# MainSheet.net
KiCad netlist of a schematic drawn in Altium Designer
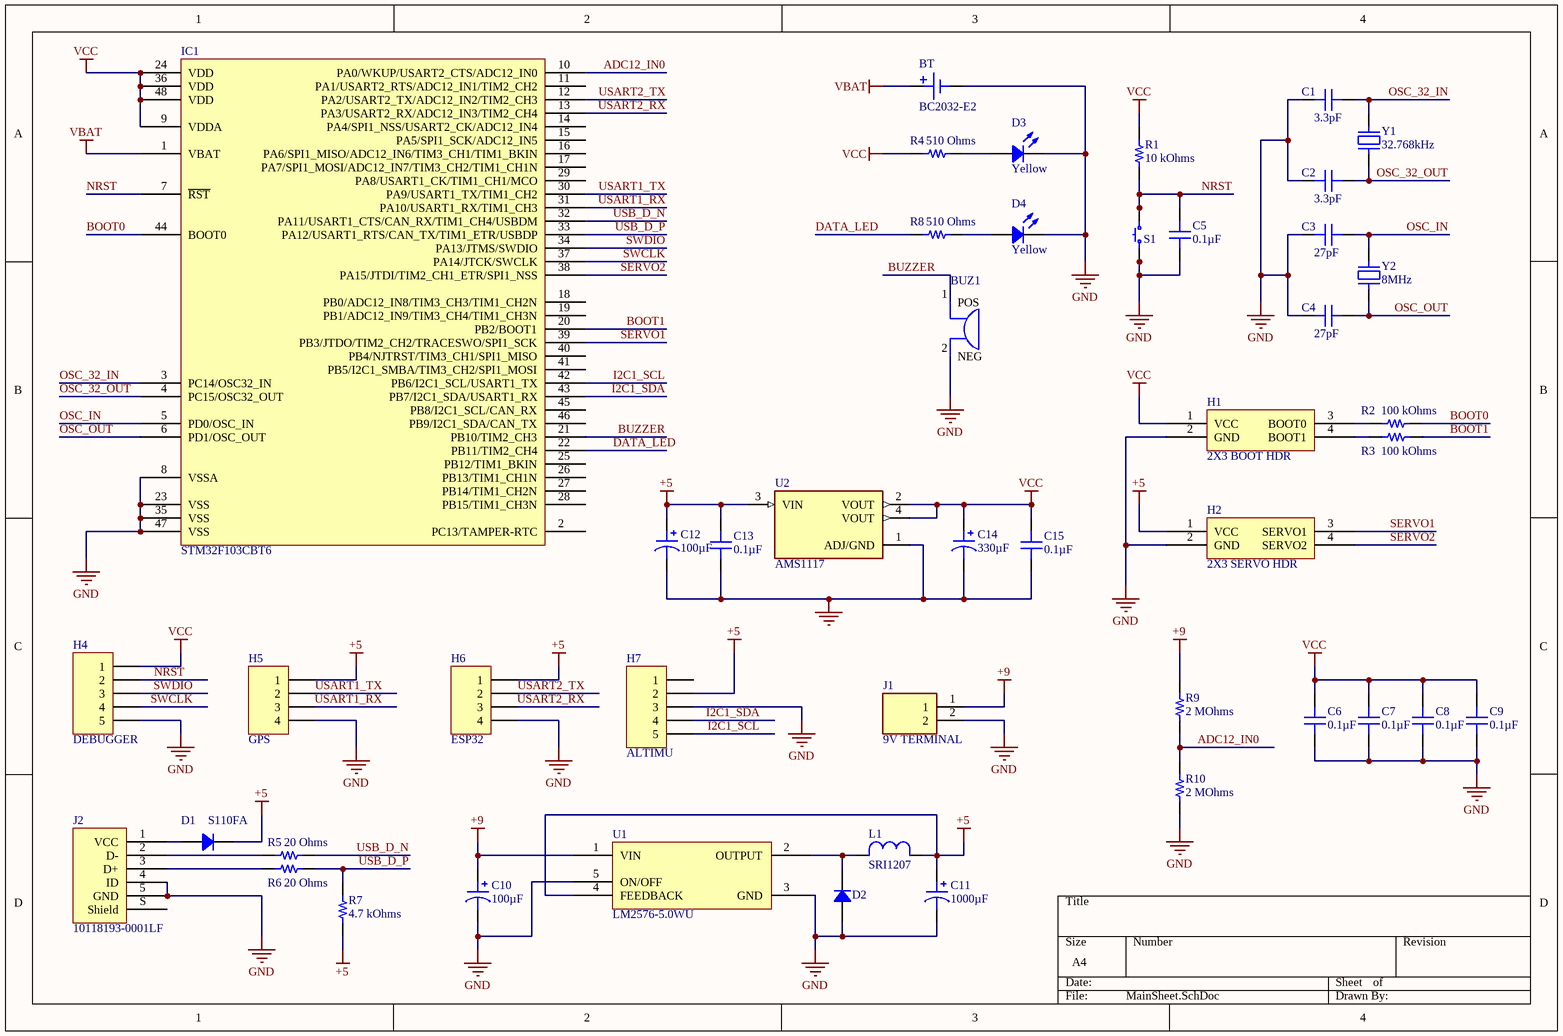
[diagram p0: MainSheet.SchDoc]

(export (version "E")
  (design (tool "Eeschema 10.0.6"))
  (components
    (comp (ref "BT")
      (value "BC2032-E2")
      (footprint "MPD_BC2032-E2")
      (description "BATTERY HOLDER COIN 20MM PC PIN")
      (fields (field (name "MF") "MPD _Memory"))
      (libsource (lib "BC2032-E2") (part "BC2032-E2"))
    )
    (comp (ref "BUZ1")
      (value "MCKPM-G1201A-K4037")
      (footprint "XDCR_MCKPM-G1201A-K4037")
      (description "Magnetic Buzzer & Transducer MCKPM-G1201A-K4037")
      (fields (field (name "MF") "Multicomp"))
      (libsource (lib "MCKPM-G1201A-K4037 (2)") (part "MCKPM-G1201A-K4037"))
    )
    (comp (ref "C1")
      (value "3.3pF")
      (footprint "CAP 0603_1608")
      (description "CAP CER 3.3PF 50V NP0 0603")
      (fields (field (name "PART NUMBER") "06035U3R3CAT2A") (field (name "MANUFACTURER") "AVX Corporation"))
      (libsource (lib "Celestial Altium Library - altium_library") (part "Capacitor"))
    )
    (comp (ref "C2")
      (value "3.3pF")
      (footprint "CAP 0603_1608")
      (description "CAP CER 3.3PF 50V NP0 0603")
      (fields (field (name "PART NUMBER") "06035U3R3CAT2A") (field (name "MANUFACTURER") "AVX Corporation"))
      (libsource (lib "Celestial Altium Library - altium_library") (part "Capacitor"))
    )
    (comp (ref "C3")
      (value "27pF")
      (footprint "CAP 0603_1608")
      (description "CAP CER 27PF 250V NP0 0603")
      (fields
        (field (name "PART NUMBER") "600S270FW250XT")
        (field (name "MANUFACTURER") "American Technical Ceramics")
      )
      (libsource (lib "Celestial Altium Library - altium_library") (part "Capacitor"))
    )
    (comp (ref "C4")
      (value "27pF")
      (footprint "CAP 0603_1608")
      (description "CAP CER 27PF 250V NP0 0603")
      (fields
        (field (name "PART NUMBER") "600S270FW250XT")
        (field (name "MANUFACTURER") "American Technical Ceramics")
      )
      (libsource (lib "Celestial Altium Library - altium_library") (part "Capacitor"))
    )
    (comp (ref "C5")
      (value "0.1µF")
      (footprint "CAP 0603_1608")
      (description "CAP CER 0.1UF 25V X7R 0603")
      (fields (field (name "PART NUMBER") "885012206071") (field (name "MANUFACTURER") "Würth Elektronik"))
      (libsource (lib "Celestial Altium Library - altium_library") (part "Capacitor"))
    )
    (comp (ref "C6")
      (value "0.1µF")
      (footprint "CAP 0603_1608")
      (description "CAP CER 0.1UF 25V X7R 0603")
      (fields (field (name "PART NUMBER") "885012206071") (field (name "MANUFACTURER") "Würth Elektronik"))
      (libsource (lib "Celestial Altium Library - altium_library") (part "Capacitor"))
    )
    (comp (ref "C7")
      (value "0.1µF")
      (footprint "CAP 0603_1608")
      (description "CAP CER 0.1UF 25V X7R 0603")
      (fields (field (name "PART NUMBER") "885012206071") (field (name "MANUFACTURER") "Würth Elektronik"))
      (libsource (lib "Celestial Altium Library - altium_library") (part "Capacitor"))
    )
    (comp (ref "C8")
      (value "0.1µF")
      (footprint "CAP 0603_1608")
      (description "CAP CER 0.1UF 25V X7R 0603")
      (fields (field (name "PART NUMBER") "885012206071") (field (name "MANUFACTURER") "Würth Elektronik"))
      (libsource (lib "Celestial Altium Library - altium_library") (part "Capacitor"))
    )
    (comp (ref "C9")
      (value "0.1µF")
      (footprint "CAP 0603_1608")
      (description "CAP CER 0.1UF 25V X7R 0603")
      (fields (field (name "PART NUMBER") "885012206071") (field (name "MANUFACTURER") "Würth Elektronik"))
      (libsource (lib "Celestial Altium Library - altium_library") (part "Capacitor"))
    )
    (comp (ref "C10")
      (value "100µF")
      (footprint "CAP POL 2917_7343")
      (description "CAP TANT 100UF 10% 16V 2917")
      (fields (field (name "PART NUMBER") "T495X107K016ATE080") (field (name "MANUFACTURER") "KEMET"))
      (libsource (lib "Celestial Altium Library - altium_library") (part "Polarised Capacitor"))
    )
    (comp (ref "C11")
      (value "1000µF")
      (footprint "CAP POL 2917_7343")
      (description "CAP TANT 1000UF 10% 6.3V 2917")
      (fields (field (name "PART NUMBER") "T491X108K006AT") (field (name "MANUFACTURER") "KEMET"))
      (libsource (lib "Celestial Altium Library - altium_library") (part "Polarised Capacitor"))
    )
    (comp (ref "C12")
      (value "100µF")
      (footprint "CAP POL 2917_7343")
      (description "CAP TANT 100UF 10% 20V 2917")
      (fields (field (name "PART NUMBER") "TR3D107K020C0080") (field (name "MANUFACTURER") "Vishay Sprague"))
      (libsource (lib "Celestial Altium Library - altium_library") (part "Polarised Capacitor"))
    )
    (comp (ref "C13")
      (value "0.1µF")
      (footprint "CAP 0805_2012")
      (description "CAP CER 0805 10% X8R 50V 100NF")
      (fields (field (name "PART NUMBER") "AC0805KKX8R9BB104") (field (name "MANUFACTURER") "Yageo"))
      (libsource (lib "Celestial Altium Library - altium_library") (part "Capacitor"))
    )
    (comp (ref "C14")
      (value "330µF")
      (footprint "CAP POL 2917_7343")
      (description "CAP TANT 330UF 10% 6.3V 2917")
      (fields (field (name "PART NUMBER") "T494D337K006AT") (field (name "MANUFACTURER") "KEMET"))
      (libsource (lib "Celestial Altium Library - altium_library") (part "Polarised Capacitor"))
    )
    (comp (ref "C15")
      (value "0.1µF")
      (footprint "CAP 0805_2012")
      (description "CAP CER 0805 10% X8R 50V 100NF")
      (fields (field (name "PART NUMBER") "AC0805KKX8R9BB104") (field (name "MANUFACTURER") "Yageo"))
      (libsource (lib "Celestial Altium Library - altium_library") (part "Capacitor"))
    )
    (comp (ref "D1")
      (value "S110FA")
      (footprint "SOD-123W")
      (description "DIODE SCHOTTKY 100V 1A SOD123FA")
      (fields (field (name "MANUFACTURER") "ON Semiconductor"))
      (libsource (lib "Celestial Altium Library - altium_library") (part "Diode"))
    )
    (comp (ref "D2")
      (value "B360Q-13-F")
      (footprint "DO214AB SMC")
      (description "DIODE SCHOTTKY 60V 3A SMC")
      (fields (field (name "MANUFACTURER") "Diodes Incorporated"))
      (libsource (lib "Celestial Altium Library - altium_library") (part "Diode"))
    )
    (comp (ref "D3")
      (value "Yellow")
      (footprint "LED 1206_3216 YELLOW")
      (description "LED YELLOW CLEAR SMD")
      (fields (field (name "PART NUMBER") "FKY1105W-TR") (field (name "MANUFACTURER") "Stanley Electric Co"))
      (libsource (lib "Celestial Altium Library - altium_library") (part "LED"))
    )
    (comp (ref "D4")
      (value "Yellow")
      (footprint "LED 1206_3216 YELLOW")
      (description "LED YELLOW CLEAR SMD")
      (fields (field (name "PART NUMBER") "FKY1105W-TR") (field (name "MANUFACTURER") "Stanley Electric Co"))
      (libsource (lib "Celestial Altium Library - altium_library") (part "LED"))
    )
    (comp (ref "H1")
      (value "2X3 BOOT HDR")
      (footprint "2x3 Male Header")
      (description "2x3 2.54mm Male Header")
      (libsource (lib "2x3 Male Header") (part "2X3 BOOT HDR"))
    )
    (comp (ref "H2")
      (value "2X3 SERVO HDR")
      (footprint "2x3 Male Header")
      (description "2x3 2.54mm Male Header")
      (libsource (lib "2x3 Male Header") (part "2X3 BOOT HDR"))
    )
    (comp (ref "H4")
      (value "DEBUGGER")
      (footprint "HDR1X5")
      (description "1x5 2.54mm Male Header")
      (fields (field (name "PUBLISHER") "Altium Limited"))
      (libsource (lib "Miscellaneous Connectors") (part "Header 5"))
    )
    (comp (ref "H5")
      (value "GPS")
      (footprint "HDR1X4")
      (description "1x4 2.54mm Male Header")
      (fields (field (name "PUBLISHER") "Altium Limited"))
      (libsource (lib "Miscellaneous Connectors") (part "Header 4"))
    )
    (comp (ref "H6")
      (value "ESP32")
      (footprint "HDR1X4")
      (description "1x4 2.54mm Male Header")
      (fields (field (name "PUBLISHER") "Altium Limited"))
      (libsource (lib "Miscellaneous Connectors") (part "Header 4"))
    )
    (comp (ref "H7")
      (value "ALTIMU")
      (footprint "HDR1X5")
      (description "1x5 2.54mm Male Header")
      (fields (field (name "PUBLISHER") "Altium Limited"))
      (libsource (lib "Miscellaneous Connectors") (part "Header 5"))
    )
    (comp (ref "IC1")
      (value "STM32F103CBT6")
      (footprint "ST LQFP-48 7X7MM")
      (description "IC MCU 32BIT 128KB FLASH 48LQFP")
      (fields (field (name "MANUFACTURER") "STMicroelectronics"))
      (libsource (lib "Celestial Altium Library - altium_library") (part "ST STM32F103 48PIN"))
    )
    (comp (ref "J1")
      (value "9V TERMINAL")
      (footprint "TE_796683-2")
      (description "Wire to Board 2 Position 5 mm Pitch 30-12 AWG Euro Style Terminal Block")
      (fields (field (name "MF") "TE Connectivity") (field (name "MP") "796683-2"))
      (libsource (lib "796683-2") (part "796683-2"))
    )
    (comp (ref "J2")
      (value "10118193-0001LF")
      (footprint "FCI USB 10118193-0001LF")
      (description "CONN RCPT USB2.0 MICRO B SMD R/A")
      (fields (field (name "MANUFACTURER") "Amphenol ICC (FCI)"))
      (libsource (lib "Celestial Altium Library - altium_library") (part "USB 2.0 Type B Micro"))
    )
    (comp (ref "L1")
      (value "SRI1207")
      (footprint "PCBComponent_1")
      (libsource (lib "SRI1207") (part "SRI1207"))
    )
    (comp (ref "R1")
      (value "10 kOhms")
      (footprint "RES 0603_1608")
      (description "RES 10K OHM 0.1% 1/5W 0603")
      (fields
        (field (name "PART NUMBER") "RS73F1JTTD1002B")
        (field (name "MANUFACTURER") "KOA Speer Electronics, Inc.")
      )
      (libsource (lib "Celestial Altium Library - altium_library") (part "Resistor"))
    )
    (comp (ref "R2")
      (value "100 kOhms")
      (footprint "RES 0603_1608")
      (description "RES SMD 100K OHM 0.5% 1/8W 0603")
      (fields
        (field (name "PART NUMBER") "MCT06030D1003DP500")
        (field (name "MANUFACTURER") "Vishay Beyschlag")
      )
      (libsource (lib "Celestial Altium Library - altium_library") (part "Resistor"))
    )
    (comp (ref "R3")
      (value "100 kOhms")
      (footprint "RES 0603_1608")
      (description "RES SMD 100K OHM 0.5% 1/8W 0603")
      (fields
        (field (name "PART NUMBER") "MCT06030D1003DP500")
        (field (name "MANUFACTURER") "Vishay Beyschlag")
      )
      (libsource (lib "Celestial Altium Library - altium_library") (part "Resistor"))
    )
    (comp (ref "R4")
      (value "510 Ohms")
      (footprint "RES 1206_3216")
      (description "RES 510 OHM 1% 1/4W 1206")
      (fields
        (field (name "PART NUMBER") "RK73H2BTTD5100F")
        (field (name "MANUFACTURER") "KOA Speer Electronics, Inc.")
      )
      (libsource (lib "Celestial Altium Library - altium_library") (part "Resistor"))
    )
    (comp (ref "R5")
      (value "20 Ohms")
      (footprint "RES 0603_1608")
      (description "RES SMD 20 OHM 0.1% 1/6W 0603")
      (fields
        (field (name "PART NUMBER") "RP73PF1J20RBTDF")
        (field (name "MANUFACTURER") "TE Connectivity Passive Product")
      )
      (libsource (lib "Celestial Altium Library - altium_library") (part "Resistor"))
    )
    (comp (ref "R6")
      (value "20 Ohms")
      (footprint "RES 0603_1608")
      (description "RES SMD 20 OHM 0.1% 1/6W 0603")
      (fields
        (field (name "PART NUMBER") "RP73PF1J20RBTDF")
        (field (name "MANUFACTURER") "TE Connectivity Passive Product")
      )
      (libsource (lib "Celestial Altium Library - altium_library") (part "Resistor"))
    )
    (comp (ref "R7")
      (value "4.7 kOhms")
      (footprint "RES 0603_1608")
      (description "RES SMD 4.7K OHM 1% 1/10W 0603")
      (fields (field (name "PART NUMBER") "AT0603FRE074K7L") (field (name "MANUFACTURER") "Yageo"))
      (libsource (lib "Celestial Altium Library - altium_library") (part "Resistor"))
    )
    (comp (ref "R8")
      (value "510 Ohms")
      (footprint "RES 1206_3216")
      (description "RES 510 OHM 1% 1/4W 1206")
      (fields
        (field (name "PART NUMBER") "RK73H2BTTD5100F")
        (field (name "MANUFACTURER") "KOA Speer Electronics, Inc.")
      )
      (libsource (lib "Celestial Altium Library - altium_library") (part "Resistor"))
    )
    (comp (ref "R9")
      (value "2 MOhms")
      (footprint "RES 1206_3216")
      (description "RES 2M OHM 0.1% 1/4W 1206")
      (fields (field (name "PART NUMBER") "TNPW12062M00BEEN") (field (name "MANUFACTURER") "Vishay Dale"))
      (libsource (lib "Celestial Altium Library - altium_library") (part "Resistor"))
    )
    (comp (ref "R10")
      (value "2 MOhms")
      (footprint "RES 1206_3216")
      (description "RES 2M OHM 0.1% 1/4W 1206")
      (fields (field (name "PART NUMBER") "TNPW12062M00BEEN") (field (name "MANUFACTURER") "Vishay Dale"))
      (libsource (lib "Celestial Altium Library - altium_library") (part "Resistor"))
    )
    (comp (ref "S1")
      (value "FSM4JSMATR")
      (footprint "TE FSM4JSMA")
      (description "SWITCH TACTILE SPST-NO 0.05A 24V")
      (fields (field (name "MANUFACTURER") "TE Connectivity ALCOSWITCH Switches"))
      (libsource (lib "Celestial Altium Library - altium_library") (part "SPST-NO 4 PIN"))
    )
    (comp (ref "U1")
      (value "LM2576-5.0WU")
      (footprint "DPAK6P170_1524X459L254X81N")
      (fields (field (name "MF") "Microchip"))
      (libsource (lib "LM2576-5.0WU") (part "LM2576-5.0WU"))
    )
    (comp (ref "U2")
      (value "AMS1117")
      (footprint "SOT229P700X180-4N")
      (description "IC-1117 5V SOT223 T/R SMD AMS")
      (fields (field (name "MF") "Seeed Technology"))
      (libsource (lib "AMS1117") (part "AMS1117"))
    )
    (comp (ref "Y1")
      (value "32.768kHz")
      (footprint "ABRACON ABS07")
      (description "CRYSTAL 32.7680KHZ 6PF SMD")
      (fields
        (field (name "PART NUMBER") "ABS07-120-32.768KHZ-T")
        (field (name "MANUFACTURER") "Abracon LLC")
      )
      (libsource (lib "Celestial Altium Library - altium_library") (part "Abracon Crystal ABS07"))
    )
    (comp (ref "Y2")
      (value "8MHz")
      (footprint "ABRACON ABLS")
      (description "CRYSTAL 8.0000MHZ 18PF SMD")
      (fields (field (name "PART NUMBER") "ABLS-8.000MHZ-B2-T") (field (name "MANUFACTURER") "Abracon LLC"))
      (libsource (lib "Celestial Altium Library - altium_library") (part "Abracon Crystal ABLS"))
    )
  )
  (nets
    (net (code "1") (name "+5") (class "Default")
      (node (ref "C11") (pin "1") (pinfunction "1_1") (pintype "passive"))
      (node (ref "C12") (pin "1") (pinfunction "1_1") (pintype "passive"))
      (node (ref "C13") (pin "2") (pinfunction "2_2") (pintype "passive"))
      (node (ref "D1") (pin "2") (pinfunction "2_2") (pintype "passive"))
      (node (ref "H2") (pin "1") (pinfunction "VCC_1") (pintype "power_in"))
      (node (ref "H5") (pin "1") (pinfunction "1_1") (pintype "passive"))
      (node (ref "H6") (pin "1") (pinfunction "1_1") (pintype "passive"))
      (node (ref "H7") (pin "2") (pinfunction "2_2") (pintype "passive"))
      (node (ref "L1") (pin "2") (pinfunction "2_2") (pintype "passive"))
      (node (ref "R7") (pin "1") (pinfunction "1_1") (pintype "passive"))
      (node (ref "U1") (pin "4") (pinfunction "FEEDBACK_4") (pintype "passive"))
      (node (ref "U2") (pin "3") (pinfunction "VIN_3") (pintype "input"))
    )
    (net (code "2") (name "+9") (class "Default")
      (node (ref "C10") (pin "1") (pinfunction "1_1") (pintype "passive"))
      (node (ref "J1") (pin "1") (pinfunction "1_1") (pintype "passive"))
      (node (ref "R9") (pin "2") (pinfunction "2_2") (pintype "passive"))
      (node (ref "U1") (pin "1") (pinfunction "VIN_1") (pintype "passive"))
    )
    (net (code "3") (name "/ADC12_IN0") (class "Default")
      (node (ref "IC1") (pin "10") (pinfunction "PA0/WKUP/USART2_CTS/ADC12_IN0_10") (pintype "passive"))
      (node (ref "R10") (pin "2") (pinfunction "2_2") (pintype "passive"))
      (node (ref "R9") (pin "1") (pinfunction "1_1") (pintype "passive"))
    )
    (net (code "4") (name "/BOOT0") (class "Default")
      (node (ref "IC1") (pin "44") (pinfunction "BOOT0_44") (pintype "passive"))
      (node (ref "R2") (pin "2") (pinfunction "2_2") (pintype "passive"))
    )
    (net (code "5") (name "/BOOT1") (class "Default")
      (node (ref "IC1") (pin "20") (pinfunction "PB2/BOOT1_20") (pintype "passive"))
      (node (ref "R3") (pin "2") (pinfunction "2_2") (pintype "passive"))
    )
    (net (code "6") (name "/BUZZER") (class "Default")
      (node (ref "BUZ1") (pin "1") (pinfunction "POS_1") (pintype "passive"))
      (node (ref "IC1") (pin "21") (pinfunction "PB10/TIM2_CH3_21") (pintype "passive"))
    )
    (net (code "7") (name "/DATA_LED") (class "Default")
      (node (ref "IC1") (pin "22") (pinfunction "PB11/TIM2_CH4_22") (pintype "passive"))
      (node (ref "R8") (pin "1") (pinfunction "1_1") (pintype "passive"))
    )
    (net (code "8") (name "/I2C1_SCL") (class "Default")
      (node (ref "H7") (pin "5") (pinfunction "5_5") (pintype "passive"))
      (node (ref "IC1") (pin "42") (pinfunction "PB6/I2C1_SCL/USART1_TX_42") (pintype "passive"))
    )
    (net (code "9") (name "/I2C1_SDA") (class "Default")
      (node (ref "H7") (pin "4") (pinfunction "4_4") (pintype "passive"))
      (node (ref "IC1") (pin "43") (pinfunction "PB7/I2C1_SDA/USART1_RX_43") (pintype "passive"))
    )
    (net (code "10") (name "/NRST") (class "Default")
      (node (ref "C5") (pin "2") (pinfunction "2_2") (pintype "passive"))
      (node (ref "H4") (pin "2") (pinfunction "2_2") (pintype "passive"))
      (node (ref "IC1") (pin "7") (pinfunction "~{RST}_7") (pintype "passive"))
      (node (ref "R1") (pin "1") (pinfunction "1_1") (pintype "passive"))
      (node (ref "S1") (pin "3") (pinfunction "3_3") (pintype "passive"))
      (node (ref "S1") (pin "4") (pinfunction "4_4") (pintype "passive"))
    )
    (net (code "11") (name "/OSC_32_IN") (class "Default")
      (node (ref "C1") (pin "2") (pinfunction "2_2") (pintype "passive"))
      (node (ref "IC1") (pin "3") (pinfunction "PC14/OSC32_IN_3") (pintype "passive"))
      (node (ref "Y1") (pin "2") (pinfunction "2_2") (pintype "passive"))
    )
    (net (code "12") (name "/OSC_32_OUT") (class "Default")
      (node (ref "C2") (pin "2") (pinfunction "2_2") (pintype "passive"))
      (node (ref "IC1") (pin "4") (pinfunction "PC15/OSC32_OUT_4") (pintype "passive"))
      (node (ref "Y1") (pin "1") (pinfunction "1_1") (pintype "passive"))
    )
    (net (code "13") (name "/OSC_IN") (class "Default")
      (node (ref "C3") (pin "1") (pinfunction "1_1") (pintype "passive"))
      (node (ref "IC1") (pin "5") (pinfunction "PD0/OSC_IN_5") (pintype "passive"))
      (node (ref "Y2") (pin "2") (pinfunction "2_2") (pintype "passive"))
    )
    (net (code "14") (name "/OSC_OUT") (class "Default")
      (node (ref "C4") (pin "1") (pinfunction "1_1") (pintype "passive"))
      (node (ref "IC1") (pin "6") (pinfunction "PD1/OSC_OUT_6") (pintype "passive"))
      (node (ref "Y2") (pin "1") (pinfunction "1_1") (pintype "passive"))
    )
    (net (code "15") (name "/SERVO1") (class "Default")
      (node (ref "H2") (pin "3") (pinfunction "BOOT0_3") (pintype "passive"))
      (node (ref "IC1") (pin "39") (pinfunction "PB3/JTDO/TIM2_CH2/TRACESWO/SPI1_SCK_39") (pintype "passive"))
    )
    (net (code "16") (name "/SERVO2") (class "Default")
      (node (ref "H2") (pin "4") (pinfunction "BOOT1_4") (pintype "passive"))
      (node (ref "IC1") (pin "38") (pinfunction "PA15/JTDI/TIM2_CH1_ETR/SPI1_NSS_38") (pintype "passive"))
    )
    (net (code "17") (name "/SWCLK") (class "Default")
      (node (ref "H4") (pin "4") (pinfunction "4_4") (pintype "passive"))
      (node (ref "IC1") (pin "37") (pinfunction "PA14/JTCK/SWCLK_37") (pintype "passive"))
    )
    (net (code "18") (name "/SWDIO") (class "Default")
      (node (ref "H4") (pin "3") (pinfunction "3_3") (pintype "passive"))
      (node (ref "IC1") (pin "34") (pinfunction "PA13/JTMS/SWDIO_34") (pintype "passive"))
    )
    (net (code "19") (name "/USART1_RX") (class "Default")
      (node (ref "H5") (pin "3") (pinfunction "3_3") (pintype "passive"))
      (node (ref "IC1") (pin "31") (pinfunction "PA10/USART1_RX/TIM1_CH3_31") (pintype "passive"))
    )
    (net (code "20") (name "/USART1_TX") (class "Default")
      (node (ref "H5") (pin "2") (pinfunction "2_2") (pintype "passive"))
      (node (ref "IC1") (pin "30") (pinfunction "PA9/USART1_TX/TIM1_CH2_30") (pintype "passive"))
    )
    (net (code "21") (name "/USART2_RX") (class "Default")
      (node (ref "H6") (pin "3") (pinfunction "3_3") (pintype "passive"))
      (node (ref "IC1") (pin "13") (pinfunction "PA3/USART2_RX/ADC12_IN3/TIM2_CH4_13") (pintype "passive"))
    )
    (net (code "22") (name "/USART2_TX") (class "Default")
      (node (ref "H6") (pin "2") (pinfunction "2_2") (pintype "passive"))
      (node (ref "IC1") (pin "12") (pinfunction "PA2/USART2_TX/ADC12_IN2/TIM2_CH3_12") (pintype "passive"))
    )
    (net (code "23") (name "/USB_D_N") (class "Default")
      (node (ref "IC1") (pin "32") (pinfunction "PA11/USART1_CTS/CAN_RX/TIM1_CH4/USBDM_32") (pintype "passive"))
      (node (ref "R5") (pin "2") (pinfunction "2_2") (pintype "passive"))
    )
    (net (code "24") (name "/USB_D_P") (class "Default")
      (node (ref "IC1") (pin "33") (pinfunction "PA12/USART1_RTS/CAN_TX/TIM1_ETR/USBDP_33") (pintype "passive"))
      (node (ref "R6") (pin "2") (pinfunction "2_2") (pintype "passive"))
      (node (ref "R7") (pin "2") (pinfunction "2_2") (pintype "passive"))
    )
    (net (code "25") (name "GND") (class "Default")
      (node (ref "BT") (pin "N") (pinfunction "N_N") (pintype "passive"))
      (node (ref "BUZ1") (pin "2") (pinfunction "NEG_2") (pintype "passive"))
      (node (ref "C1") (pin "1") (pinfunction "1_1") (pintype "passive"))
      (node (ref "C10") (pin "2") (pinfunction "2_2") (pintype "passive"))
      (node (ref "C11") (pin "2") (pinfunction "2_2") (pintype "passive"))
      (node (ref "C12") (pin "2") (pinfunction "2_2") (pintype "passive"))
      (node (ref "C13") (pin "1") (pinfunction "1_1") (pintype "passive"))
      (node (ref "C14") (pin "2") (pinfunction "2_2") (pintype "passive"))
      (node (ref "C15") (pin "1") (pinfunction "1_1") (pintype "passive"))
      (node (ref "C2") (pin "1") (pinfunction "1_1") (pintype "passive"))
      (node (ref "C3") (pin "2") (pinfunction "2_2") (pintype "passive"))
      (node (ref "C4") (pin "2") (pinfunction "2_2") (pintype "passive"))
      (node (ref "C5") (pin "1") (pinfunction "1_1") (pintype "passive"))
      (node (ref "C6") (pin "1") (pinfunction "1_1") (pintype "passive"))
      (node (ref "C7") (pin "1") (pinfunction "1_1") (pintype "passive"))
      (node (ref "C8") (pin "1") (pinfunction "1_1") (pintype "passive"))
      (node (ref "C9") (pin "1") (pinfunction "1_1") (pintype "passive"))
      (node (ref "D2") (pin "1") (pinfunction "1_1") (pintype "passive"))
      (node (ref "D3") (pin "2") (pinfunction "2_2") (pintype "passive"))
      (node (ref "D4") (pin "2") (pinfunction "2_2") (pintype "passive"))
      (node (ref "H1") (pin "2") (pinfunction "GND_2") (pintype "power_in"))
      (node (ref "H2") (pin "2") (pinfunction "GND_2") (pintype "power_in"))
      (node (ref "H4") (pin "5") (pinfunction "5_5") (pintype "passive"))
      (node (ref "H5") (pin "4") (pinfunction "4_4") (pintype "passive"))
      (node (ref "H6") (pin "4") (pinfunction "4_4") (pintype "passive"))
      (node (ref "H7") (pin "3") (pinfunction "3_3") (pintype "passive"))
      (node (ref "IC1") (pin "23") (pinfunction "VSS_23") (pintype "passive"))
      (node (ref "IC1") (pin "35") (pinfunction "VSS_35") (pintype "passive"))
      (node (ref "IC1") (pin "47") (pinfunction "VSS_47") (pintype "passive"))
      (node (ref "IC1") (pin "8") (pinfunction "VSSA_8") (pintype "passive"))
      (node (ref "J1") (pin "2") (pinfunction "2_2") (pintype "passive"))
      (node (ref "J2") (pin "4") (pinfunction "ID_4") (pintype "passive"))
      (node (ref "J2") (pin "5") (pinfunction "GND_5") (pintype "passive"))
      (node (ref "R10") (pin "1") (pinfunction "1_1") (pintype "passive"))
      (node (ref "S1") (pin "1") (pinfunction "1_1") (pintype "passive"))
      (node (ref "S1") (pin "2") (pinfunction "2_2") (pintype "passive"))
      (node (ref "U1") (pin "3") (pinfunction "GND_3") (pintype "passive"))
      (node (ref "U1") (pin "5") (pinfunction "ON/OFF_5") (pintype "passive"))
      (node (ref "U2") (pin "1") (pinfunction "ADJ/GND_1") (pintype "power_in"))
    )
    (net (code "26") (name "Net-(D3-Pad1)") (class "Default")
      (node (ref "D3") (pin "1") (pinfunction "1_1") (pintype "passive"))
      (node (ref "R4") (pin "2") (pinfunction "2_2") (pintype "passive"))
    )
    (net (code "27") (name "Net-(D4-Pad1)") (class "Default")
      (node (ref "D4") (pin "1") (pinfunction "1_1") (pintype "passive"))
      (node (ref "R8") (pin "2") (pinfunction "2_2") (pintype "passive"))
    )
    (net (code "28") (name "Net-(H1-BOOT0)") (class "Default")
      (node (ref "H1") (pin "3") (pinfunction "BOOT0_3") (pintype "passive"))
      (node (ref "R2") (pin "1") (pinfunction "1_1") (pintype "passive"))
    )
    (net (code "29") (name "Net-(H1-BOOT1)") (class "Default")
      (node (ref "H1") (pin "4") (pinfunction "BOOT1_4") (pintype "passive"))
      (node (ref "R3") (pin "1") (pinfunction "1_1") (pintype "passive"))
    )
    (net (code "30") (name "Net-(J2-D+)") (class "Default")
      (node (ref "J2") (pin "3") (pinfunction "D+_3") (pintype "passive"))
      (node (ref "R6") (pin "1") (pinfunction "1_1") (pintype "passive"))
    )
    (net (code "31") (name "Net-(J2-D-)") (class "Default")
      (node (ref "J2") (pin "2") (pinfunction "D-_2") (pintype "passive"))
      (node (ref "R5") (pin "1") (pinfunction "1_1") (pintype "passive"))
    )
    (net (code "32") (name "Net-(J2-VCC)") (class "Default")
      (node (ref "D1") (pin "1") (pinfunction "1_1") (pintype "passive"))
      (node (ref "J2") (pin "1") (pinfunction "VCC_1") (pintype "passive"))
    )
    (net (code "33") (name "Net-(U1-OUTPUT)") (class "Default")
      (node (ref "D2") (pin "2") (pinfunction "2_2") (pintype "passive"))
      (node (ref "L1") (pin "1") (pinfunction "1_1") (pintype "passive"))
      (node (ref "U1") (pin "2") (pinfunction "OUTPUT_2") (pintype "passive"))
    )
    (net (code "34") (name "VBAT") (class "Default")
      (node (ref "BT") (pin "P") (pinfunction "P_P") (pintype "passive"))
      (node (ref "IC1") (pin "1") (pinfunction "VBAT_1") (pintype "passive"))
    )
    (net (code "35") (name "VCC") (class "Default")
      (node (ref "C14") (pin "1") (pinfunction "1_1") (pintype "passive"))
      (node (ref "C15") (pin "2") (pinfunction "2_2") (pintype "passive"))
      (node (ref "C6") (pin "2") (pinfunction "2_2") (pintype "passive"))
      (node (ref "C7") (pin "2") (pinfunction "2_2") (pintype "passive"))
      (node (ref "C8") (pin "2") (pinfunction "2_2") (pintype "passive"))
      (node (ref "C9") (pin "2") (pinfunction "2_2") (pintype "passive"))
      (node (ref "H1") (pin "1") (pinfunction "VCC_1") (pintype "power_in"))
      (node (ref "H4") (pin "1") (pinfunction "1_1") (pintype "passive"))
      (node (ref "IC1") (pin "24") (pinfunction "VDD_24") (pintype "passive"))
      (node (ref "IC1") (pin "36") (pinfunction "VDD_36") (pintype "passive"))
      (node (ref "IC1") (pin "48") (pinfunction "VDD_48") (pintype "passive"))
      (node (ref "IC1") (pin "9") (pinfunction "VDDA_9") (pintype "passive"))
      (node (ref "R1") (pin "2") (pinfunction "2_2") (pintype "passive"))
      (node (ref "R4") (pin "1") (pinfunction "1_1") (pintype "passive"))
      (node (ref "U2") (pin "2") (pinfunction "VOUT_2") (pintype "output"))
      (node (ref "U2") (pin "4") (pinfunction "VOUT_4") (pintype "output"))
    )
    (net (code "36") (name "unconnected-(H7-Pad1)") (class "Default")
      (node (ref "H7") (pin "1") (pinfunction "1_1") (pintype "passive"))
    )
    (net (code "37") (name "unconnected-(IC1-PA1{slash}USART2_RTS{slash}ADC12_IN1{slash}TIM2_CH2-Pad11)") (class "Default")
      (node (ref "IC1") (pin "11") (pinfunction "PA1/USART2_RTS/ADC12_IN1/TIM2_CH2_11") (pintype "passive"))
    )
    (net (code "38") (name "unconnected-(IC1-PA4{slash}SPI1_NSS{slash}USART2_CK{slash}ADC12_IN4-Pad14)") (class "Default")
      (node (ref "IC1") (pin "14") (pinfunction "PA4/SPI1_NSS/USART2_CK/ADC12_IN4_14") (pintype "passive"))
    )
    (net (code "39") (name "unconnected-(IC1-PA5{slash}SPI1_SCK{slash}ADC12_IN5-Pad15)") (class "Default")
      (node (ref "IC1") (pin "15") (pinfunction "PA5/SPI1_SCK/ADC12_IN5_15") (pintype "passive"))
    )
    (net (code "40") (name "unconnected-(IC1-PA6{slash}SPI1_MISO{slash}ADC12_IN6{slash}TIM3_CH1{slash}TIM1_BKIN-Pad16)") (class "Default")
      (node (ref "IC1") (pin "16") (pinfunction "PA6/SPI1_MISO/ADC12_IN6/TIM3_CH1/TIM1_BKIN_16") (pintype "passive"))
    )
    (net (code "41") (name "unconnected-(IC1-PA7{slash}SPI1_MOSI{slash}ADC12_IN7{slash}TIM3_CH2{slash}TIM1_CH1N-Pad17)") (class "Default")
      (node (ref "IC1") (pin "17") (pinfunction "PA7/SPI1_MOSI/ADC12_IN7/TIM3_CH2/TIM1_CH1N_17") (pintype "passive"))
    )
    (net (code "42") (name "unconnected-(IC1-PA8{slash}USART1_CK{slash}TIM1_CH1{slash}MCO-Pad29)") (class "Default")
      (node (ref "IC1") (pin "29") (pinfunction "PA8/USART1_CK/TIM1_CH1/MCO_29") (pintype "passive"))
    )
    (net (code "43") (name "unconnected-(IC1-PB0{slash}ADC12_IN8{slash}TIM3_CH3{slash}TIM1_CH2N-Pad18)") (class "Default")
      (node (ref "IC1") (pin "18") (pinfunction "PB0/ADC12_IN8/TIM3_CH3/TIM1_CH2N_18") (pintype "passive"))
    )
    (net (code "44") (name "unconnected-(IC1-PB1{slash}ADC12_IN9{slash}TIM3_CH4{slash}TIM1_CH3N-Pad19)") (class "Default")
      (node (ref "IC1") (pin "19") (pinfunction "PB1/ADC12_IN9/TIM3_CH4/TIM1_CH3N_19") (pintype "passive"))
    )
    (net (code "45") (name "unconnected-(IC1-PB4{slash}NJTRST{slash}TIM3_CH1{slash}SPI1_MISO-Pad40)") (class "Default")
      (node (ref "IC1") (pin "40") (pinfunction "PB4/NJTRST/TIM3_CH1/SPI1_MISO_40") (pintype "passive"))
    )
    (net (code "46") (name "unconnected-(IC1-PB5{slash}I2C1_SMBA{slash}TIM3_CH2{slash}SPI1_MOSI-Pad41)") (class "Default")
      (node (ref "IC1") (pin "41") (pinfunction "PB5/I2C1_SMBA/TIM3_CH2/SPI1_MOSI_41") (pintype "passive"))
    )
    (net (code "47") (name "unconnected-(IC1-PB8{slash}I2C1_SCL{slash}CAN_RX-Pad45)") (class "Default")
      (node (ref "IC1") (pin "45") (pinfunction "PB8/I2C1_SCL/CAN_RX_45") (pintype "passive"))
    )
    (net (code "48") (name "unconnected-(IC1-PB9{slash}I2C1_SDA{slash}CAN_TX-Pad46)") (class "Default")
      (node (ref "IC1") (pin "46") (pinfunction "PB9/I2C1_SDA/CAN_TX_46") (pintype "passive"))
    )
    (net (code "49") (name "unconnected-(IC1-PB12{slash}TIM1_BKIN-Pad25)") (class "Default")
      (node (ref "IC1") (pin "25") (pinfunction "PB12/TIM1_BKIN_25") (pintype "passive"))
    )
    (net (code "50") (name "unconnected-(IC1-PB13{slash}TIM1_CH1N-Pad26)") (class "Default")
      (node (ref "IC1") (pin "26") (pinfunction "PB13/TIM1_CH1N_26") (pintype "passive"))
    )
    (net (code "51") (name "unconnected-(IC1-PB14{slash}TIM1_CH2N-Pad27)") (class "Default")
      (node (ref "IC1") (pin "27") (pinfunction "PB14/TIM1_CH2N_27") (pintype "passive"))
    )
    (net (code "52") (name "unconnected-(IC1-PB15{slash}TIM1_CH3N-Pad28)") (class "Default")
      (node (ref "IC1") (pin "28") (pinfunction "PB15/TIM1_CH3N_28") (pintype "passive"))
    )
    (net (code "53") (name "unconnected-(IC1-PC13{slash}TAMPER-RTC-Pad2)") (class "Default")
      (node (ref "IC1") (pin "2") (pinfunction "PC13/TAMPER-RTC_2") (pintype "passive"))
    )
    (net (code "54") (name "unconnected-(J2-Shield-PadS)") (class "Default")
      (node (ref "J2") (pin "S") (pinfunction "Shield_S") (pintype "passive"))
    )
  )
)
